# CMSIS-DAP_11U37_V100.net
KiCad netlist of a schematic drawn in Altium Designer
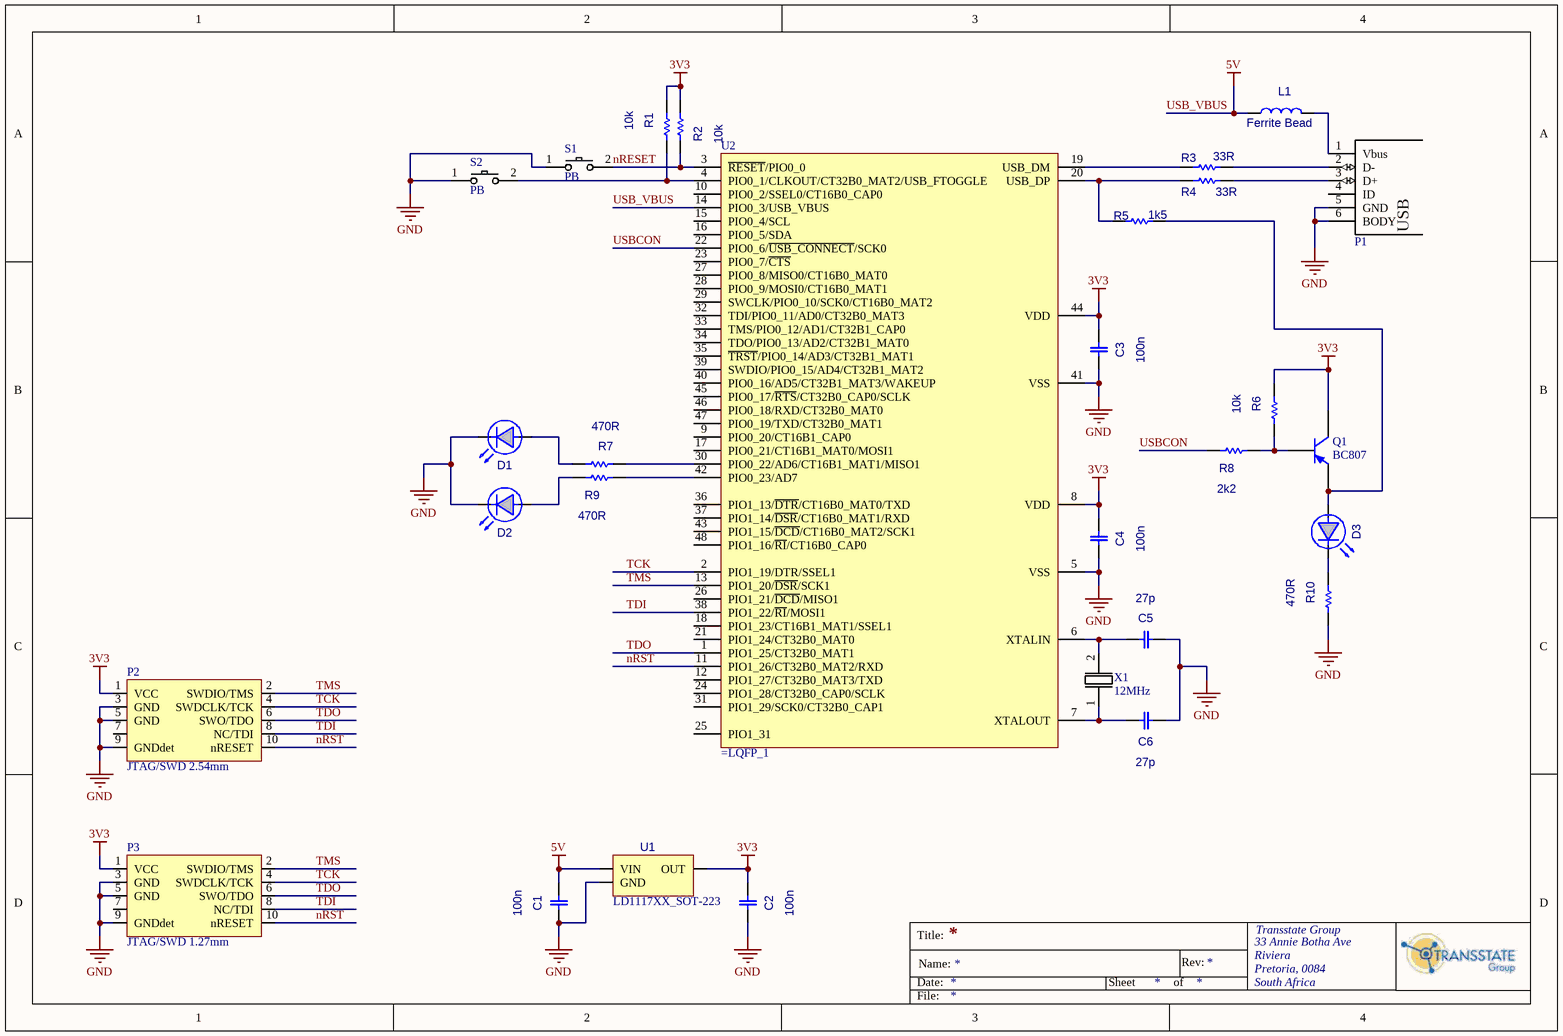
[diagram p0: CMSIS-DAP_11U37_V100.SchDoc]

(export (version "E")
  (design (tool "Eeschema 10.0.6"))
  (components
    (comp (ref "C1")
      (value "100n")
      (footprint "CAP 0603")
      (description "Capacitor Ceramic")
      (libsource (lib "altium_lib_1") (part "Capacitor Ceramic"))
    )
    (comp (ref "C2")
      (value "100n")
      (footprint "CAP 0603")
      (description "Capacitor Ceramic")
      (libsource (lib "altium_lib_1") (part "Capacitor Ceramic"))
    )
    (comp (ref "C3")
      (value "100n")
      (footprint "CAP 0603")
      (description "Capacitor Ceramic")
      (libsource (lib "altium_lib_1") (part "Capacitor Ceramic"))
    )
    (comp (ref "C4")
      (value "100n")
      (footprint "CAP 0603")
      (description "Capacitor Ceramic")
      (libsource (lib "altium_lib_1") (part "Capacitor Ceramic"))
    )
    (comp (ref "C5")
      (value "27p")
      (footprint "CAP 0603")
      (description "Capacitor Ceramic")
      (libsource (lib "altium_lib_1") (part "Capacitor Ceramic"))
    )
    (comp (ref "C6")
      (value "27p")
      (footprint "CAP 0603")
      (description "Capacitor Ceramic")
      (libsource (lib "altium_lib_1") (part "Capacitor Ceramic"))
    )
    (comp (ref "D1") (value "LED") (footprint "LED 0603") (libsource (lib "altium_lib_1") (part "LED")))
    (comp (ref "D2") (value "LED") (footprint "LED 0603") (libsource (lib "altium_lib_1") (part "LED")))
    (comp (ref "D3") (value "LED") (footprint "LED 0603") (libsource (lib "altium_lib_1") (part "LED")))
    (comp (ref "L1")
      (value "Ferrite Bead")
      (footprint "IND 0603")
      (description "Inductor")
      (libsource (lib "altium_lib_1") (part "Inductor"))
    )
    (comp (ref "P1")
      (value "USB MICRO-B")
      (footprint "USB - MICRO-B SMD")
      (libsource (lib "altium_lib_1") (part "USB MICRO-B"))
    )
    (comp (ref "P2")
      (value "JTAG/SWD 2.54mm")
      (footprint "Header IDC Box 10w 2.54mm")
      (description "CONN - 10W JTAG/SWD")
      (libsource (lib "altium_lib_1") (part "CONN - 10W JTAG/SWD"))
    )
    (comp (ref "P3")
      (value "JTAG/SWD 1.27mm")
      (footprint "Header 10W /2 1.27mm Shrouded")
      (description "CONN - 10W JTAG/SWD")
      (libsource (lib "altium_lib_1") (part "CONN - 10W JTAG/SWD"))
    )
    (comp (ref "Q1")
      (value "BC807")
      (footprint "SOT-23")
      (description "PNP Bipolar Transistor")
      (libsource (lib "altium_lib_1") (part "Transistor PNP"))
    )
    (comp (ref "R1")
      (value "10k")
      (footprint "RES 0603")
      (description "Resistor")
      (libsource (lib "altium_lib_1") (part "Resistor"))
    )
    (comp (ref "R2")
      (value "10k")
      (footprint "RES 0603")
      (description "Resistor")
      (libsource (lib "altium_lib_1") (part "Resistor"))
    )
    (comp (ref "R3")
      (value "33R")
      (footprint "RES 0603")
      (description "Resistor")
      (libsource (lib "altium_lib_1") (part "Resistor"))
    )
    (comp (ref "R4")
      (value "33R")
      (footprint "RES 0603")
      (description "Resistor")
      (libsource (lib "altium_lib_1") (part "Resistor"))
    )
    (comp (ref "R5")
      (value "1k5")
      (footprint "RES 0603")
      (description "Resistor")
      (libsource (lib "altium_lib_1") (part "Resistor"))
    )
    (comp (ref "R6")
      (value "10k")
      (footprint "RES 0603")
      (description "Resistor")
      (libsource (lib "altium_lib_1") (part "Resistor"))
    )
    (comp (ref "R7")
      (value "470R")
      (footprint "RES 0603")
      (description "Resistor")
      (libsource (lib "altium_lib_1") (part "Resistor"))
    )
    (comp (ref "R8")
      (value "2k2")
      (footprint "RES 0603")
      (description "Resistor")
      (libsource (lib "altium_lib_1") (part "Resistor"))
    )
    (comp (ref "R9")
      (value "470R")
      (footprint "RES 0603")
      (description "Resistor")
      (libsource (lib "altium_lib_1") (part "Resistor"))
    )
    (comp (ref "R10")
      (value "470R")
      (footprint "RES 0603")
      (description "Resistor")
      (libsource (lib "altium_lib_1") (part "Resistor"))
    )
    (comp (ref "S1")
      (value "PB")
      (footprint "Push Button Omron SPST")
      (libsource (lib "altium_lib_1") (part "Push Button SPST"))
    )
    (comp (ref "S2")
      (value "PB")
      (footprint "Push Button Omron SPST")
      (libsource (lib "altium_lib_1") (part "Push Button SPST"))
    )
    (comp (ref "U1")
      (value "{Value}")
      (footprint "SOT-223")
      (description "Regulator Positive")
      (fields (field (name "CODE4") "LD1117XX_SOT-223"))
      (libsource (lib "altium_lib_1") (part "Regulator Positive"))
    )
    (comp (ref "U2") (value "~") (footprint "LQFP-48") (libsource (lib "lib_ic") (part "LPC11Uxx-48")))
    (comp (ref "X1")
      (value "12MHz")
      (footprint "Crystal SMU4")
      (libsource (lib "altium_lib_1") (part "Crystal"))
    )
  )
  (nets
    (net (code "1") (name "/TCK") (class "Default")
      (node (ref "P2") (pin "4") (pinfunction "SWDCLK/TCK_4") (pintype "passive"))
      (node (ref "P3") (pin "4") (pinfunction "SWDCLK/TCK_4") (pintype "passive"))
      (node (ref "U2") (pin "2") (pinfunction "PIO1_19/DTR/SSEL1_2") (pintype "passive"))
    )
    (net (code "2") (name "/TDI") (class "Default")
      (node (ref "P2") (pin "8") (pinfunction "NC/TDI_8") (pintype "passive"))
      (node (ref "P3") (pin "8") (pinfunction "NC/TDI_8") (pintype "passive"))
      (node (ref "U2") (pin "38") (pinfunction "PIO1_22/~{RI}/MOSI1_38") (pintype "passive"))
    )
    (net (code "3") (name "/TDO") (class "Default")
      (node (ref "P2") (pin "6") (pinfunction "SWO/TDO_6") (pintype "passive"))
      (node (ref "P3") (pin "6") (pinfunction "SWO/TDO_6") (pintype "passive"))
      (node (ref "U2") (pin "1") (pinfunction "PIO1_25/CT32B0_MAT1_1") (pintype "passive"))
    )
    (net (code "4") (name "/TMS") (class "Default")
      (node (ref "P2") (pin "2") (pinfunction "SWDIO/TMS_2") (pintype "passive"))
      (node (ref "P3") (pin "2") (pinfunction "SWDIO/TMS_2") (pintype "passive"))
      (node (ref "U2") (pin "13") (pinfunction "PIO1_20/~{DSR}/SCK1_13") (pintype "passive"))
    )
    (net (code "5") (name "/USBCON") (class "Default")
      (node (ref "R8") (pin "2") (pintype "passive"))
      (node (ref "U2") (pin "22") (pinfunction "PIO0_6/~{USB_CONNECT}/SCK0_22") (pintype "passive"))
    )
    (net (code "6") (name "/nRESET") (class "Default")
      (node (ref "R2") (pin "2") (pintype "passive"))
      (node (ref "S1") (pin "2") (pinfunction "2_2") (pintype "passive"))
      (node (ref "U2") (pin "3") (pinfunction "~{RESET}/PIO0_0_3") (pintype "passive"))
    )
    (net (code "7") (name "/nRST") (class "Default")
      (node (ref "P2") (pin "10") (pinfunction "nRESET_10") (pintype "passive"))
      (node (ref "P3") (pin "10") (pinfunction "nRESET_10") (pintype "passive"))
      (node (ref "U2") (pin "11") (pinfunction "PIO1_26/CT32B0_MAT2/RXD_11") (pintype "passive"))
    )
    (net (code "8") (name "3V3") (class "Default")
      (node (ref "C2") (pin "1") (pintype "passive"))
      (node (ref "C3") (pin "1") (pintype "passive"))
      (node (ref "C4") (pin "1") (pintype "passive"))
      (node (ref "P2") (pin "1") (pinfunction "VCC_1") (pintype "passive"))
      (node (ref "P3") (pin "1") (pinfunction "VCC_1") (pintype "passive"))
      (node (ref "Q1") (pin "3") (pinfunction "C_3") (pintype "passive"))
      (node (ref "R1") (pin "2") (pintype "passive"))
      (node (ref "R2") (pin "1") (pintype "passive"))
      (node (ref "R6") (pin "2") (pintype "passive"))
      (node (ref "U1") (pin "3") (pinfunction "OUT_3") (pintype "passive"))
      (node (ref "U2") (pin "44") (pinfunction "VDD_44") (pintype "passive"))
      (node (ref "U2") (pin "8") (pinfunction "VDD_8") (pintype "passive"))
    )
    (net (code "9") (name "5V") (class "Default")
      (node (ref "C1") (pin "2") (pintype "passive"))
      (node (ref "L1") (pin "1") (pinfunction "1_1") (pintype "passive"))
      (node (ref "U1") (pin "1") (pinfunction "VIN_1") (pintype "passive"))
      (node (ref "U2") (pin "14") (pinfunction "PIO0_3/USB_VBUS_14") (pintype "passive"))
    )
    (net (code "10") (name "GND") (class "Default")
      (node (ref "C1") (pin "1") (pintype "passive"))
      (node (ref "C2") (pin "2") (pintype "passive"))
      (node (ref "C3") (pin "2") (pintype "passive"))
      (node (ref "C4") (pin "2") (pintype "passive"))
      (node (ref "C5") (pin "2") (pintype "passive"))
      (node (ref "C6") (pin "1") (pintype "passive"))
      (node (ref "D1") (pin "2") (pintype "passive"))
      (node (ref "D2") (pin "2") (pintype "passive"))
      (node (ref "P1") (pin "5") (pinfunction "GND_5") (pintype "power_in"))
      (node (ref "P1") (pin "6") (pinfunction "BODY_6") (pintype "passive"))
      (node (ref "P2") (pin "3") (pinfunction "GND_3") (pintype "passive"))
      (node (ref "P2") (pin "5") (pinfunction "GND_5") (pintype "passive"))
      (node (ref "P2") (pin "9") (pinfunction "GNDdet_9") (pintype "passive"))
      (node (ref "P3") (pin "3") (pinfunction "GND_3") (pintype "passive"))
      (node (ref "P3") (pin "5") (pinfunction "GND_5") (pintype "passive"))
      (node (ref "P3") (pin "9") (pinfunction "GNDdet_9") (pintype "passive"))
      (node (ref "R10") (pin "1") (pintype "passive"))
      (node (ref "S1") (pin "1") (pinfunction "1_1") (pintype "passive"))
      (node (ref "S2") (pin "1") (pinfunction "1_1") (pintype "passive"))
      (node (ref "U1") (pin "2") (pinfunction "GND_2") (pintype "passive"))
      (node (ref "U2") (pin "41") (pinfunction "VSS_41") (pintype "passive"))
      (node (ref "U2") (pin "5") (pinfunction "VSS_5") (pintype "passive"))
    )
    (net (code "11") (name "Net-(D1-Pad1)") (class "Default")
      (node (ref "D1") (pin "1") (pintype "passive"))
      (node (ref "R7") (pin "1") (pintype "passive"))
    )
    (net (code "12") (name "Net-(D2-Pad1)") (class "Default")
      (node (ref "D2") (pin "1") (pintype "passive"))
      (node (ref "R9") (pin "2") (pintype "passive"))
    )
    (net (code "13") (name "Net-(D3-Pad2)") (class "Default")
      (node (ref "D3") (pin "2") (pintype "passive"))
      (node (ref "R10") (pin "2") (pintype "passive"))
    )
    (net (code "14") (name "Net-(P1-D+)") (class "Default")
      (node (ref "P1") (pin "3") (pinfunction "D+_3") (pintype "bidirectional"))
      (node (ref "R4") (pin "1") (pintype "passive"))
    )
    (net (code "15") (name "Net-(P1-D-)") (class "Default")
      (node (ref "P1") (pin "2") (pinfunction "D-_2") (pintype "bidirectional"))
      (node (ref "R3") (pin "2") (pintype "passive"))
    )
    (net (code "16") (name "Net-(P1-Vbus)") (class "Default")
      (node (ref "L1") (pin "2") (pinfunction "2_2") (pintype "passive"))
      (node (ref "P1") (pin "1") (pinfunction "Vbus_1") (pintype "power_in"))
    )
    (net (code "17") (name "Net-(Q1-B)") (class "Default")
      (node (ref "Q1") (pin "1") (pinfunction "B_1") (pintype "passive"))
      (node (ref "R6") (pin "1") (pintype "passive"))
      (node (ref "R8") (pin "1") (pintype "passive"))
    )
    (net (code "18") (name "Net-(Q1-E)") (class "Default")
      (node (ref "D3") (pin "1") (pintype "passive"))
      (node (ref "Q1") (pin "2") (pinfunction "E_2") (pintype "passive"))
      (node (ref "R5") (pin "1") (pintype "passive"))
    )
    (net (code "19") (name "Net-(U2-PIO0_1{slash}CLKOUT{slash}CT32B0_MAT2{slash}USB_FTOGGLE)") (class "Default")
      (node (ref "R1") (pin "1") (pintype "passive"))
      (node (ref "S2") (pin "2") (pinfunction "2_2") (pintype "passive"))
      (node (ref "U2") (pin "4") (pinfunction "PIO0_1/CLKOUT/CT32B0_MAT2/USB_FTOGGLE_4") (pintype "passive"))
    )
    (net (code "20") (name "Net-(U2-PIO0_22{slash}AD6{slash}CT16B1_MAT1{slash}MISO1)") (class "Default")
      (node (ref "R7") (pin "2") (pintype "passive"))
      (node (ref "U2") (pin "30") (pinfunction "PIO0_22/AD6/CT16B1_MAT1/MISO1_30") (pintype "passive"))
    )
    (net (code "21") (name "Net-(U2-PIO0_23{slash}AD7)") (class "Default")
      (node (ref "R9") (pin "1") (pintype "passive"))
      (node (ref "U2") (pin "42") (pinfunction "PIO0_23/AD7_42") (pintype "passive"))
    )
    (net (code "22") (name "Net-(U2-USB_DM)") (class "Default")
      (node (ref "R3") (pin "1") (pintype "passive"))
      (node (ref "U2") (pin "19") (pinfunction "USB_DM_19") (pintype "passive"))
    )
    (net (code "23") (name "Net-(U2-USB_DP)") (class "Default")
      (node (ref "R4") (pin "2") (pintype "passive"))
      (node (ref "R5") (pin "2") (pintype "passive"))
      (node (ref "U2") (pin "20") (pinfunction "USB_DP_20") (pintype "passive"))
    )
    (net (code "24") (name "Net-(U2-XTALIN)") (class "Default")
      (node (ref "C5") (pin "1") (pintype "passive"))
      (node (ref "U2") (pin "6") (pinfunction "XTALIN_6") (pintype "passive"))
      (node (ref "X1") (pin "2") (pintype "passive"))
    )
    (net (code "25") (name "Net-(U2-XTALOUT)") (class "Default")
      (node (ref "C6") (pin "2") (pintype "passive"))
      (node (ref "U2") (pin "7") (pinfunction "XTALOUT_7") (pintype "passive"))
      (node (ref "X1") (pin "1") (pintype "passive"))
    )
    (net (code "26") (name "unconnected-(P1-ID-Pad4)") (class "Default")
      (node (ref "P1") (pin "4") (pinfunction "ID_4") (pintype "passive"))
    )
    (net (code "27") (name "unconnected-(P2-Pad7)") (class "Default")
      (node (ref "P2") (pin "7") (pinfunction "7_7") (pintype "passive"))
    )
    (net (code "28") (name "unconnected-(P3-Pad7)") (class "Default")
      (node (ref "P3") (pin "7") (pinfunction "7_7") (pintype "passive"))
    )
    (net (code "29") (name "unconnected-(U2-PIO0_2{slash}SSEL0{slash}CT16B0_CAP0-Pad10)") (class "Default")
      (node (ref "U2") (pin "10") (pinfunction "PIO0_2/SSEL0/CT16B0_CAP0_10") (pintype "passive"))
    )
    (net (code "30") (name "unconnected-(U2-PIO0_4{slash}SCL-Pad15)") (class "Default")
      (node (ref "U2") (pin "15") (pinfunction "PIO0_4/SCL_15") (pintype "passive"))
    )
    (net (code "31") (name "unconnected-(U2-PIO0_5{slash}SDA-Pad16)") (class "Default")
      (node (ref "U2") (pin "16") (pinfunction "PIO0_5/SDA_16") (pintype "passive"))
    )
    (net (code "32") (name "unconnected-(U2-PIO0_7{slash}~{CTS}-Pad23)") (class "Default")
      (node (ref "U2") (pin "23") (pinfunction "PIO0_7/~{CTS}_23") (pintype "passive"))
    )
    (net (code "33") (name "unconnected-(U2-PIO0_8{slash}MISO0{slash}CT16B0_MAT0-Pad27)") (class "Default")
      (node (ref "U2") (pin "27") (pinfunction "PIO0_8/MISO0/CT16B0_MAT0_27") (pintype "passive"))
    )
    (net (code "34") (name "unconnected-(U2-PIO0_9{slash}MOSI0{slash}CT16B0_MAT1-Pad28)") (class "Default")
      (node (ref "U2") (pin "28") (pinfunction "PIO0_9/MOSI0/CT16B0_MAT1_28") (pintype "passive"))
    )
    (net (code "35") (name "unconnected-(U2-PIO0_16{slash}AD5{slash}CT32B1_MAT3{slash}WAKEUP-Pad40)") (class "Default")
      (node (ref "U2") (pin "40") (pinfunction "PIO0_16/AD5/CT32B1_MAT3/WAKEUP_40") (pintype "passive"))
    )
    (net (code "36") (name "unconnected-(U2-PIO0_17{slash}~{RTS}{slash}CT32B0_CAP0{slash}SCLK-Pad45)") (class "Default")
      (node (ref "U2") (pin "45") (pinfunction "PIO0_17/~{RTS}/CT32B0_CAP0/SCLK_45") (pintype "passive"))
    )
    (net (code "37") (name "unconnected-(U2-PIO0_18{slash}RXD{slash}CT32B0_MAT0-Pad46)") (class "Default")
      (node (ref "U2") (pin "46") (pinfunction "PIO0_18/RXD/CT32B0_MAT0_46") (pintype "passive"))
    )
    (net (code "38") (name "unconnected-(U2-PIO0_19{slash}TXD{slash}CT32B0_MAT1-Pad47)") (class "Default")
      (node (ref "U2") (pin "47") (pinfunction "PIO0_19/TXD/CT32B0_MAT1_47") (pintype "passive"))
    )
    (net (code "39") (name "unconnected-(U2-PIO0_20{slash}CT16B1_CAP0-Pad9)") (class "Default")
      (node (ref "U2") (pin "9") (pinfunction "PIO0_20/CT16B1_CAP0_9") (pintype "passive"))
    )
    (net (code "40") (name "unconnected-(U2-PIO0_21{slash}CT16B1_MAT0{slash}MOSI1-Pad17)") (class "Default")
      (node (ref "U2") (pin "17") (pinfunction "PIO0_21/CT16B1_MAT0/MOSI1_17") (pintype "passive"))
    )
    (net (code "41") (name "unconnected-(U2-PIO1_13{slash}~{DTR}{slash}CT16B0_MAT0{slash}TXD-Pad36)") (class "Default")
      (node (ref "U2") (pin "36") (pinfunction "PIO1_13/~{DTR}/CT16B0_MAT0/TXD_36") (pintype "passive"))
    )
    (net (code "42") (name "unconnected-(U2-PIO1_14{slash}~{DSR}{slash}CT16B0_MAT1{slash}RXD-Pad37)") (class "Default")
      (node (ref "U2") (pin "37") (pinfunction "PIO1_14/~{DSR}/CT16B0_MAT1/RXD_37") (pintype "passive"))
    )
    (net (code "43") (name "unconnected-(U2-PIO1_15{slash}~{DCD}{slash}CT16B0_MAT2{slash}SCK1-Pad43)") (class "Default")
      (node (ref "U2") (pin "43") (pinfunction "PIO1_15/~{DCD}/CT16B0_MAT2/SCK1_43") (pintype "passive"))
    )
    (net (code "44") (name "unconnected-(U2-PIO1_16{slash}~{RI}{slash}CT16B0_CAP0-Pad48)") (class "Default")
      (node (ref "U2") (pin "48") (pinfunction "PIO1_16/~{RI}/CT16B0_CAP0_48") (pintype "passive"))
    )
    (net (code "45") (name "unconnected-(U2-PIO1_21{slash}~{DCD}{slash}MISO1-Pad26)") (class "Default")
      (node (ref "U2") (pin "26") (pinfunction "PIO1_21/~{DCD}/MISO1_26") (pintype "passive"))
    )
    (net (code "46") (name "unconnected-(U2-PIO1_23{slash}CT16B1_MAT1{slash}SSEL1-Pad18)") (class "Default")
      (node (ref "U2") (pin "18") (pinfunction "PIO1_23/CT16B1_MAT1/SSEL1_18") (pintype "passive"))
    )
    (net (code "47") (name "unconnected-(U2-PIO1_24{slash}CT32B0_MAT0-Pad21)") (class "Default")
      (node (ref "U2") (pin "21") (pinfunction "PIO1_24/CT32B0_MAT0_21") (pintype "passive"))
    )
    (net (code "48") (name "unconnected-(U2-PIO1_27{slash}CT32B0_MAT3{slash}TXD-Pad12)") (class "Default")
      (node (ref "U2") (pin "12") (pinfunction "PIO1_27/CT32B0_MAT3/TXD_12") (pintype "passive"))
    )
    (net (code "49") (name "unconnected-(U2-PIO1_28{slash}CT32B0_CAP0{slash}SCLK-Pad24)") (class "Default")
      (node (ref "U2") (pin "24") (pinfunction "PIO1_28/CT32B0_CAP0/SCLK_24") (pintype "passive"))
    )
    (net (code "50") (name "unconnected-(U2-PIO1_29{slash}SCK0{slash}CT32B0_CAP1-Pad31)") (class "Default")
      (node (ref "U2") (pin "31") (pinfunction "PIO1_29/SCK0/CT32B0_CAP1_31") (pintype "passive"))
    )
    (net (code "51") (name "unconnected-(U2-PIO1_31-Pad25)") (class "Default")
      (node (ref "U2") (pin "25") (pinfunction "PIO1_31_25") (pintype "passive"))
    )
    (net (code "52") (name "unconnected-(U2-SWCLK{slash}PIO0_10{slash}SCK0{slash}CT16B0_MAT2-Pad29)") (class "Default")
      (node (ref "U2") (pin "29") (pinfunction "SWCLK/PIO0_10/SCK0/CT16B0_MAT2_29") (pintype "passive"))
    )
    (net (code "53") (name "unconnected-(U2-SWDIO{slash}PIO0_15{slash}AD4{slash}CT32B1_MAT2-Pad39)") (class "Default")
      (node (ref "U2") (pin "39") (pinfunction "SWDIO/PIO0_15/AD4/CT32B1_MAT2_39") (pintype "passive"))
    )
    (net (code "54") (name "unconnected-(U2-TDI{slash}PIO0_11{slash}AD0{slash}CT32B0_MAT3-Pad32)") (class "Default")
      (node (ref "U2") (pin "32") (pinfunction "TDI/PIO0_11/AD0/CT32B0_MAT3_32") (pintype "passive"))
    )
    (net (code "55") (name "unconnected-(U2-TDO{slash}PIO0_13{slash}AD2{slash}CT32B1_MAT0-Pad34)") (class "Default")
      (node (ref "U2") (pin "34") (pinfunction "TDO/PIO0_13/AD2/CT32B1_MAT0_34") (pintype "passive"))
    )
    (net (code "56") (name "unconnected-(U2-TMS{slash}PIO0_12{slash}AD1{slash}CT32B1_CAP0-Pad33)") (class "Default")
      (node (ref "U2") (pin "33") (pinfunction "TMS/PIO0_12/AD1/CT32B1_CAP0_33") (pintype "passive"))
    )
    (net (code "57") (name "unconnected-(U2-~{TRST}{slash}PIO0_14{slash}AD3{slash}CT32B1_MAT1-Pad35)") (class "Default")
      (node (ref "U2") (pin "35") (pinfunction "~{TRST}/PIO0_14/AD3/CT32B1_MAT1_35") (pintype "passive"))
    )
  )
)
